# espduino-12.net
KiCad netlist of a schematic drawn in EAGLE
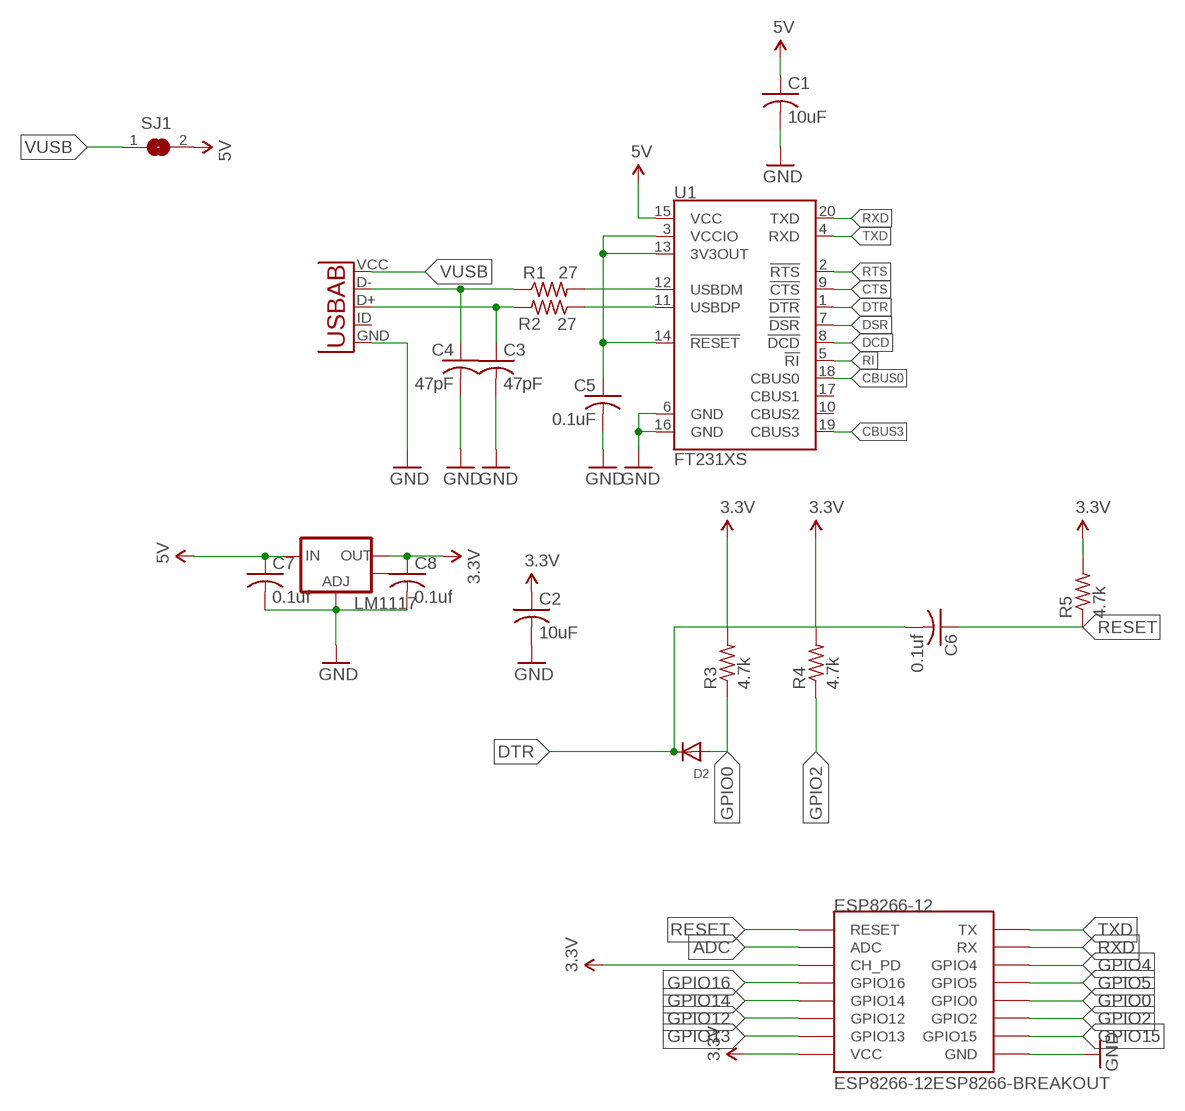
[diagram p0: schematic, sheet 1]

(export (version "E")
  (design (tool "Eeschema 10.0.6"))
  (components
    (comp (ref "C1")
      (value "10uF")
      (footprint "eagle-import:C0603")
      (libsource (lib "eagle-import") (part "C-USC0603"))
    )
    (comp (ref "C2")
      (value "10uF")
      (footprint "eagle-import:C0603")
      (libsource (lib "eagle-import") (part "C-USC0603"))
    )
    (comp (ref "C3")
      (value "47pF")
      (footprint "eagle-import:C0603")
      (libsource (lib "eagle-import") (part "C-USC0603"))
    )
    (comp (ref "C4")
      (value "47pF")
      (footprint "eagle-import:C0603")
      (libsource (lib "eagle-import") (part "C-USC0603"))
    )
    (comp (ref "C5")
      (value "0.1uF")
      (footprint "eagle-import:C0603")
      (libsource (lib "eagle-import") (part "C-USC0603"))
    )
    (comp (ref "C6")
      (value "0.1uf")
      (footprint "eagle-import:C0603")
      (libsource (lib "eagle-import") (part "C-USC0603"))
    )
    (comp (ref "C7")
      (value "0.1uf")
      (footprint "eagle-import:C0603")
      (libsource (lib "eagle-import") (part "C-USC0603"))
    )
    (comp (ref "C8")
      (value "0.1uf")
      (footprint "eagle-import:C0603")
      (libsource (lib "eagle-import") (part "C-USC0603"))
    )
    (comp (ref "D2")
      (value "DIODESOT23_REFLOW")
      (footprint "eagle-import:SOT23-R")
      (libsource (lib "eagle-import") (part "DIODESOT23_REFLOW"))
    )
    (comp (ref "ESP8266-12")
      (value "ESP8266-12ESP8266-BREAKOUT")
      (footprint "eagle-import:ESP8266-12-EXT-HEADERS")
      (libsource (lib "eagle-import") (part "ESP8266-12ESP8266-BREAKOUT"))
    )
    (comp (ref "LM1117")
      (value "V_REG_LM1117SOT223")
      (footprint "eagle-import:SOT223")
      (libsource (lib "eagle-import") (part "V_REG_LM1117SOT223"))
    )
    (comp (ref "R1")
      (value "27")
      (footprint "eagle-import:R0603")
      (libsource (lib "eagle-import") (part "R-US_R0603"))
    )
    (comp (ref "R2")
      (value "27")
      (footprint "eagle-import:R0603")
      (libsource (lib "eagle-import") (part "R-US_R0603"))
    )
    (comp (ref "R3")
      (value "4.7k")
      (footprint "eagle-import:R0603")
      (libsource (lib "eagle-import") (part "R-US_R0603"))
    )
    (comp (ref "R4")
      (value "4.7k")
      (footprint "eagle-import:R0603")
      (libsource (lib "eagle-import") (part "R-US_R0603"))
    )
    (comp (ref "R5")
      (value "4.7k")
      (footprint "eagle-import:R0603")
      (libsource (lib "eagle-import") (part "R-US_R0603"))
    )
    (comp (ref "SJ1")
      (value "SJCUTTABLE")
      (footprint "eagle-import:SJ-CUTTABLE")
      (libsource (lib "eagle-import") (part "SJCUTTABLE"))
    )
    (comp (ref "U1")
      (value "FT231XS")
      (footprint "eagle-import:SSOP20_L")
      (libsource (lib "eagle-import") (part "FT231XS"))
    )
    (comp (ref "U2")
      (value "USB-AB")
      (footprint "eagle-import:MICRO-USB-A01SB141B1")
      (libsource (lib "eagle-import") (part "USB-AB"))
    )
  )
  (nets
    (net (code "1") (name "3.3V") (class "Default")
      (node (ref "C2") (pin "1") (pinfunction "1_1") (pintype "passive"))
      (node (ref "C8") (pin "1") (pinfunction "1_1") (pintype "passive"))
      (node (ref "ESP8266-12") (pin "CH_PD") (pinfunction "CH_PD_CH_PD") (pintype "bidirectional"))
      (node (ref "ESP8266-12") (pin "VCC") (pinfunction "VCC_VCC") (pintype "bidirectional"))
      (node (ref "ESP8266-12") (pin "VCC_P") (pinfunction "VCC_VCC_P") (pintype "bidirectional"))
      (node (ref "LM1117") (pin "2") (pinfunction "OUT_2") (pintype "output"))
      (node (ref "R3") (pin "2") (pinfunction "2_2") (pintype "passive"))
      (node (ref "R4") (pin "2") (pinfunction "2_2") (pintype "passive"))
      (node (ref "R5") (pin "2") (pinfunction "2_2") (pintype "passive"))
    )
    (net (code "2") (name "5V") (class "Default")
      (node (ref "C1") (pin "1") (pinfunction "1_1") (pintype "passive"))
      (node (ref "C7") (pin "1") (pinfunction "1_1") (pintype "passive"))
      (node (ref "LM1117") (pin "3") (pinfunction "IN_3") (pintype "input"))
      (node (ref "SJ1") (pin "2") (pinfunction "2_2") (pintype "passive"))
      (node (ref "U1") (pin "15") (pinfunction "VCC_15") (pintype "bidirectional"))
    )
    (net (code "3") (name "ADC") (class "Default")
      (node (ref "ESP8266-12") (pin "ADC") (pinfunction "ADC_ADC") (pintype "bidirectional"))
      (node (ref "ESP8266-12") (pin "ADC_P") (pinfunction "ADC_ADC_P") (pintype "bidirectional"))
    )
    (net (code "4") (name "CBUS0") (class "Default")
      (node (ref "U1") (pin "18") (pinfunction "CBUS0_18") (pintype "bidirectional"))
    )
    (net (code "5") (name "CBUS3") (class "Default")
      (node (ref "U1") (pin "19") (pinfunction "CBUS3_19") (pintype "bidirectional"))
    )
    (net (code "6") (name "CTS") (class "Default")
      (node (ref "U1") (pin "9") (pinfunction "~{CTS}_9") (pintype "bidirectional"))
    )
    (net (code "7") (name "DCD") (class "Default")
      (node (ref "U1") (pin "8") (pinfunction "~{DCD}_8") (pintype "bidirectional"))
    )
    (net (code "8") (name "DSR") (class "Default")
      (node (ref "U1") (pin "7") (pinfunction "~{DSR}_7") (pintype "bidirectional"))
    )
    (net (code "9") (name "DTR") (class "Default")
      (node (ref "C6") (pin "2") (pinfunction "2_2") (pintype "passive"))
      (node (ref "D2") (pin "3") (pinfunction "C_3") (pintype "passive"))
      (node (ref "U1") (pin "1") (pinfunction "~{DTR}_1") (pintype "bidirectional"))
    )
    (net (code "10") (name "GND") (class "Default")
      (node (ref "C1") (pin "2") (pinfunction "2_2") (pintype "passive"))
      (node (ref "C2") (pin "2") (pinfunction "2_2") (pintype "passive"))
      (node (ref "C3") (pin "2") (pinfunction "2_2") (pintype "passive"))
      (node (ref "C4") (pin "2") (pinfunction "2_2") (pintype "passive"))
      (node (ref "C5") (pin "2") (pinfunction "2_2") (pintype "passive"))
      (node (ref "C7") (pin "2") (pinfunction "2_2") (pintype "passive"))
      (node (ref "C8") (pin "2") (pinfunction "2_2") (pintype "passive"))
      (node (ref "ESP8266-12") (pin "GND") (pinfunction "GND_GND") (pintype "bidirectional"))
      (node (ref "ESP8266-12") (pin "GND_P") (pinfunction "GND_GND_P") (pintype "bidirectional"))
      (node (ref "LM1117") (pin "1") (pinfunction "ADJ_1") (pintype "input"))
      (node (ref "U1") (pin "16") (pinfunction "GND_16") (pintype "bidirectional"))
      (node (ref "U1") (pin "6") (pinfunction "GND_6") (pintype "bidirectional"))
      (node (ref "U2") (pin "GND") (pinfunction "GND_GND") (pintype "bidirectional"))
    )
    (net (code "11") (name "GPIO0") (class "Default")
      (node (ref "D2") (pin "1") (pinfunction "A_1") (pintype "passive"))
      (node (ref "ESP8266-12") (pin "GPIO0") (pinfunction "GPIO0_GPIO0") (pintype "bidirectional"))
      (node (ref "ESP8266-12") (pin "GPIO0_P") (pinfunction "GPIO0_GPIO0_P") (pintype "bidirectional"))
      (node (ref "R3") (pin "1") (pinfunction "1_1") (pintype "passive"))
    )
    (net (code "12") (name "GPIO2") (class "Default")
      (node (ref "ESP8266-12") (pin "GPIO2") (pinfunction "GPIO2_GPIO2") (pintype "bidirectional"))
      (node (ref "ESP8266-12") (pin "GPIO2_P") (pinfunction "GPIO2_GPIO2_P") (pintype "bidirectional"))
      (node (ref "R4") (pin "1") (pinfunction "1_1") (pintype "passive"))
    )
    (net (code "13") (name "GPIO4") (class "Default")
      (node (ref "ESP8266-12") (pin "GPIO4") (pinfunction "GPIO4_GPIO4") (pintype "bidirectional"))
      (node (ref "ESP8266-12") (pin "GPIO4_P") (pinfunction "GPIO4_GPIO4_P") (pintype "bidirectional"))
    )
    (net (code "14") (name "GPIO5") (class "Default")
      (node (ref "ESP8266-12") (pin "GPIO5") (pinfunction "GPIO5_GPIO5") (pintype "bidirectional"))
      (node (ref "ESP8266-12") (pin "GPIO5_P") (pinfunction "GPIO5_GPIO5_P") (pintype "bidirectional"))
    )
    (net (code "15") (name "GPIO12") (class "Default")
      (node (ref "ESP8266-12") (pin "GPIO12") (pinfunction "GPIO12_GPIO12") (pintype "bidirectional"))
      (node (ref "ESP8266-12") (pin "GPIO12_P") (pinfunction "GPIO12_GPIO12_P") (pintype "bidirectional"))
    )
    (net (code "16") (name "GPIO13") (class "Default")
      (node (ref "ESP8266-12") (pin "GPIO13") (pinfunction "GPIO13_GPIO13") (pintype "bidirectional"))
      (node (ref "ESP8266-12") (pin "GPIO13_P") (pinfunction "GPIO13_GPIO13_P") (pintype "bidirectional"))
    )
    (net (code "17") (name "GPIO14") (class "Default")
      (node (ref "ESP8266-12") (pin "GPIO14") (pinfunction "GPIO14_GPIO14") (pintype "bidirectional"))
      (node (ref "ESP8266-12") (pin "GPIO14_P") (pinfunction "GPIO14_GPIO14_P") (pintype "bidirectional"))
    )
    (net (code "18") (name "GPIO15") (class "Default")
      (node (ref "ESP8266-12") (pin "GPIO15") (pinfunction "GPIO15_GPIO15") (pintype "bidirectional"))
      (node (ref "ESP8266-12") (pin "GPIO15_P") (pinfunction "GPIO15_GPIO15_P") (pintype "bidirectional"))
    )
    (net (code "19") (name "GPIO16") (class "Default")
      (node (ref "ESP8266-12") (pin "GPIO16") (pinfunction "GPIO16_GPIO16") (pintype "bidirectional"))
      (node (ref "ESP8266-12") (pin "GPIO_16_P") (pinfunction "GPIO16_GPIO_16_P") (pintype "bidirectional"))
    )
    (net (code "20") (name "Net-(C3-Pad1)") (class "Default")
      (node (ref "C3") (pin "1") (pinfunction "1_1") (pintype "passive"))
      (node (ref "R2") (pin "2") (pinfunction "2_2") (pintype "passive"))
      (node (ref "U2") (pin "D+") (pinfunction "D+_D+") (pintype "bidirectional"))
    )
    (net (code "21") (name "Net-(C4-Pad1)") (class "Default")
      (node (ref "C4") (pin "1") (pinfunction "1_1") (pintype "passive"))
      (node (ref "R1") (pin "1") (pinfunction "1_1") (pintype "passive"))
      (node (ref "U2") (pin "D-") (pinfunction "D-_D-") (pintype "bidirectional"))
    )
    (net (code "22") (name "Net-(U1-3V3OUT)") (class "Default")
      (node (ref "C5") (pin "1") (pinfunction "1_1") (pintype "passive"))
      (node (ref "U1") (pin "13") (pinfunction "3V3OUT_13") (pintype "bidirectional"))
      (node (ref "U1") (pin "14") (pinfunction "~{RESET}_14") (pintype "bidirectional"))
      (node (ref "U1") (pin "3") (pinfunction "VCCIO_3") (pintype "bidirectional"))
    )
    (net (code "23") (name "Net-(U1-USBDM)") (class "Default")
      (node (ref "R1") (pin "2") (pinfunction "2_2") (pintype "passive"))
      (node (ref "U1") (pin "12") (pinfunction "USBDM_12") (pintype "bidirectional"))
    )
    (net (code "24") (name "Net-(U1-USBDP)") (class "Default")
      (node (ref "R2") (pin "1") (pinfunction "1_1") (pintype "passive"))
      (node (ref "U1") (pin "11") (pinfunction "USBDP_11") (pintype "bidirectional"))
    )
    (net (code "25") (name "RESET") (class "Default")
      (node (ref "C6") (pin "1") (pinfunction "1_1") (pintype "passive"))
      (node (ref "ESP8266-12") (pin "RESET") (pinfunction "RESET_RESET") (pintype "bidirectional"))
      (node (ref "R5") (pin "1") (pinfunction "1_1") (pintype "passive"))
    )
    (net (code "26") (name "RI") (class "Default")
      (node (ref "U1") (pin "5") (pinfunction "~{RI}_5") (pintype "bidirectional"))
    )
    (net (code "27") (name "RTS") (class "Default")
      (node (ref "U1") (pin "2") (pinfunction "~{RTS}_2") (pintype "bidirectional"))
    )
    (net (code "28") (name "RXD") (class "Default")
      (node (ref "ESP8266-12") (pin "RX") (pinfunction "RX_RX") (pintype "bidirectional"))
      (node (ref "U1") (pin "20") (pinfunction "TXD_20") (pintype "bidirectional"))
    )
    (net (code "29") (name "TXD") (class "Default")
      (node (ref "ESP8266-12") (pin "TX") (pinfunction "TX_TX") (pintype "bidirectional"))
      (node (ref "U1") (pin "4") (pinfunction "RXD_4") (pintype "bidirectional"))
    )
    (net (code "30") (name "VUSB") (class "Default")
      (node (ref "SJ1") (pin "1") (pinfunction "1_1") (pintype "passive"))
      (node (ref "U2") (pin "VCC") (pinfunction "VBUS_VCC") (pintype "bidirectional"))
    )
    (net (code "31") (name "unconnected-(LM1117-OUT-Pad4)") (class "Default")
      (node (ref "LM1117") (pin "4") (pinfunction "OUT_4") (pintype "output"))
    )
    (net (code "32") (name "unconnected-(U1-CBUS1-Pad17)") (class "Default")
      (node (ref "U1") (pin "17") (pinfunction "CBUS1_17") (pintype "bidirectional"))
    )
    (net (code "33") (name "unconnected-(U1-CBUS2-Pad10)") (class "Default")
      (node (ref "U1") (pin "10") (pinfunction "CBUS2_10") (pintype "bidirectional"))
    )
    (net (code "34") (name "unconnected-(U2-USBID-PadID)") (class "Default")
      (node (ref "U2") (pin "ID") (pinfunction "USBID_ID") (pintype "bidirectional"))
    )
  )
)
